# fpga-power.net
KiCad netlist of a schematic drawn in Altium Designer
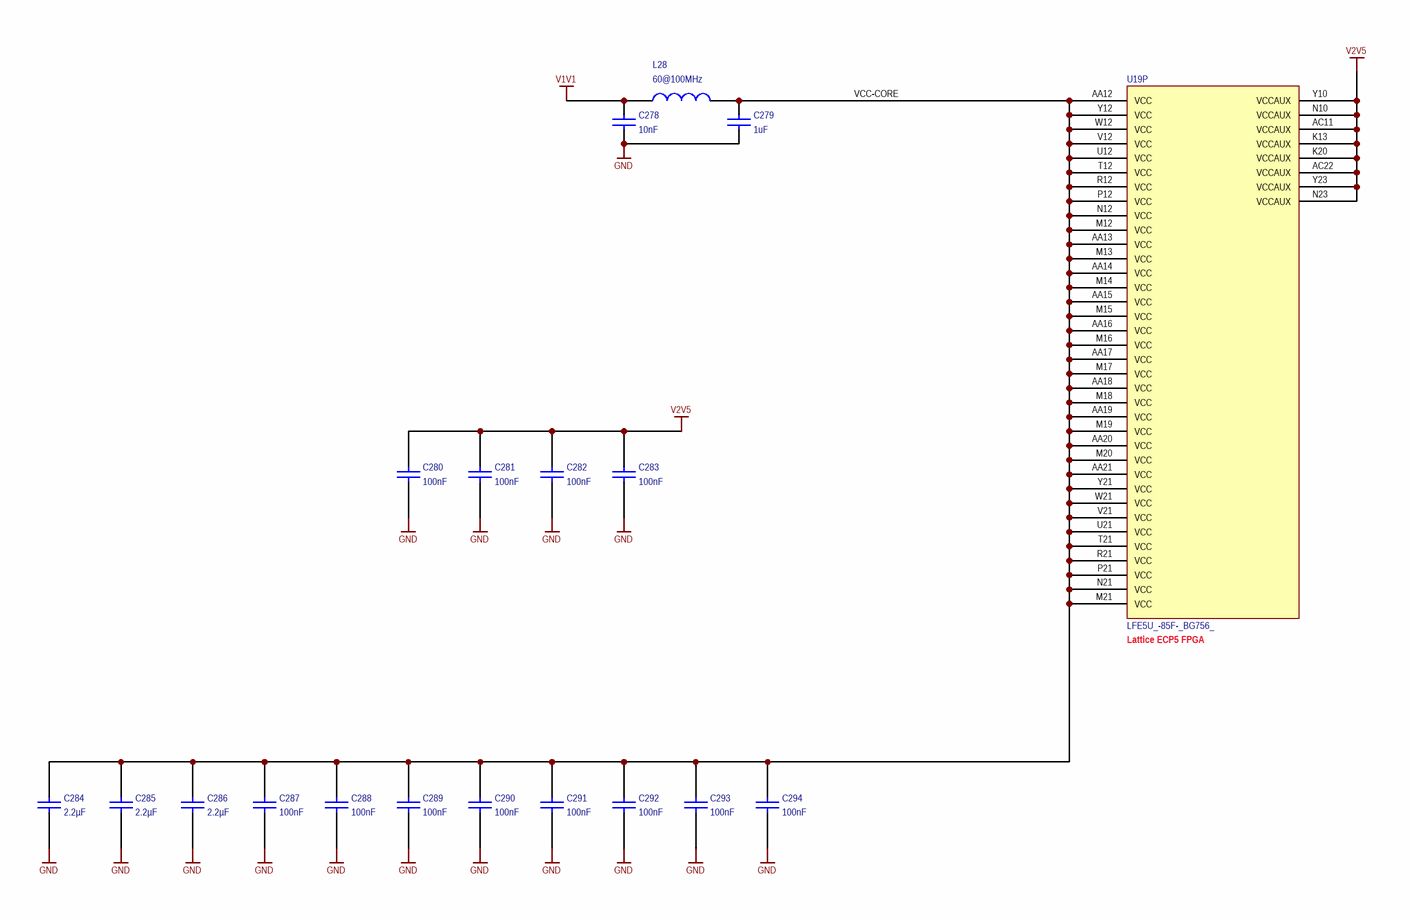
[diagram p0: fpga-power.SchDoc]

(export (version "E")
  (design (tool "Eeschema 10.0.6"))
  (components
    (comp (ref "C278")
      (value "10nF")
      (footprint "generic:0402")
      (description "Ceramic Capacitor 10nF ±10% 25V X7R 0402")
      (fields (field (name "VOLTAGE") "25V") (field (name "MANUFACTURER") "Murata"))
      (libsource (lib "Graviton") (part "CAP 0402"))
    )
    (comp (ref "C279")
      (value "1uF")
      (footprint "generic:0402")
      (description "Ceramic Capacitor 1uF ±10% 10V X5R 0402")
      (fields (field (name "VOLTAGE") "10V") (field (name "MANUFACTURER") "Murata"))
      (libsource (lib "Graviton") (part "CAP 0402"))
    )
    (comp (ref "C280")
      (value "100nF")
      (footprint "generic:CAPC1005X56N")
      (description "Ceramic Capacitor 100nF ±10% 16V X7R 0402")
      (fields (field (name "MANUFACTURER") "Murata") (field (name "TOLERANCE") "±10%"))
      (libsource (lib "murata") (part "GRM155R71A104KA01J"))
    )
    (comp (ref "C281")
      (value "100nF")
      (footprint "generic:CAPC1005X56N")
      (description "Ceramic Capacitor 100nF ±10% 16V X7R 0402")
      (fields (field (name "MANUFACTURER") "Murata") (field (name "TOLERANCE") "±10%"))
      (libsource (lib "murata") (part "GRM155R71A104KA01J"))
    )
    (comp (ref "C282")
      (value "100nF")
      (footprint "generic:CAPC1005X56N")
      (description "Ceramic Capacitor 100nF ±10% 16V X7R 0402")
      (fields (field (name "MANUFACTURER") "Murata") (field (name "TOLERANCE") "±10%"))
      (libsource (lib "murata") (part "GRM155R71A104KA01J"))
    )
    (comp (ref "C283")
      (value "100nF")
      (footprint "generic:CAPC1005X56N")
      (description "Ceramic Capacitor 100nF ±10% 16V X7R 0402")
      (fields (field (name "MANUFACTURER") "Murata") (field (name "TOLERANCE") "±10%"))
      (libsource (lib "murata") (part "GRM155R71A104KA01J"))
    )
    (comp (ref "C284")
      (value "2.2µF")
      (footprint "generic:CAPC1608X90N")
      (description "Ceramic Capacitor 2.2uF ±10% 10V X7R 0603")
      (fields (field (name "MANUFACTURER") "Murata") (field (name "TOLERANCE") "±10%"))
      (libsource (lib "murata") (part "GRM188R71A225KE15D"))
    )
    (comp (ref "C285")
      (value "2.2µF")
      (footprint "generic:CAPC1608X90N")
      (description "Ceramic Capacitor 2.2uF ±10% 10V X7R 0603")
      (fields (field (name "MANUFACTURER") "Murata") (field (name "TOLERANCE") "±10%"))
      (libsource (lib "murata") (part "GRM188R71A225KE15D"))
    )
    (comp (ref "C286")
      (value "2.2µF")
      (footprint "generic:CAPC1608X90N")
      (description "Ceramic Capacitor 2.2uF ±10% 10V X7R 0603")
      (fields (field (name "MANUFACTURER") "Murata") (field (name "TOLERANCE") "±10%"))
      (libsource (lib "murata") (part "GRM188R71A225KE15D"))
    )
    (comp (ref "C287")
      (value "100nF")
      (footprint "generic:CAPC1005X56N")
      (description "Ceramic Capacitor 100nF ±10% 16V X7R 0402")
      (fields (field (name "MANUFACTURER") "Murata") (field (name "TOLERANCE") "±10%"))
      (libsource (lib "murata") (part "GRM155R71A104KA01J"))
    )
    (comp (ref "C288")
      (value "100nF")
      (footprint "generic:CAPC1005X56N")
      (description "Ceramic Capacitor 100nF ±10% 16V X7R 0402")
      (fields (field (name "MANUFACTURER") "Murata") (field (name "TOLERANCE") "±10%"))
      (libsource (lib "murata") (part "GRM155R71A104KA01J"))
    )
    (comp (ref "C289")
      (value "100nF")
      (footprint "generic:CAPC1005X56N")
      (description "Ceramic Capacitor 100nF ±10% 16V X7R 0402")
      (fields (field (name "MANUFACTURER") "Murata") (field (name "TOLERANCE") "±10%"))
      (libsource (lib "murata") (part "GRM155R71A104KA01J"))
    )
    (comp (ref "C290")
      (value "100nF")
      (footprint "generic:CAPC1005X56N")
      (description "Ceramic Capacitor 100nF ±10% 16V X7R 0402")
      (fields (field (name "MANUFACTURER") "Murata") (field (name "TOLERANCE") "±10%"))
      (libsource (lib "murata") (part "GRM155R71A104KA01J"))
    )
    (comp (ref "C291")
      (value "100nF")
      (footprint "generic:CAPC1005X56N")
      (description "Ceramic Capacitor 100nF ±10% 16V X7R 0402")
      (fields (field (name "MANUFACTURER") "Murata") (field (name "TOLERANCE") "±10%"))
      (libsource (lib "murata") (part "GRM155R71A104KA01J"))
    )
    (comp (ref "C292")
      (value "100nF")
      (footprint "generic:CAPC1005X56N")
      (description "Ceramic Capacitor 100nF ±10% 16V X7R 0402")
      (fields (field (name "MANUFACTURER") "Murata") (field (name "TOLERANCE") "±10%"))
      (libsource (lib "murata") (part "GRM155R71A104KA01J"))
    )
    (comp (ref "C293")
      (value "100nF")
      (footprint "generic:CAPC1005X56N")
      (description "Ceramic Capacitor 100nF ±10% 16V X7R 0402")
      (fields (field (name "MANUFACTURER") "Murata") (field (name "TOLERANCE") "±10%"))
      (libsource (lib "murata") (part "GRM155R71A104KA01J"))
    )
    (comp (ref "C294")
      (value "100nF")
      (footprint "generic:CAPC1005X56N")
      (description "Ceramic Capacitor 100nF ±10% 16V X7R 0402")
      (fields (field (name "MANUFACTURER") "Murata") (field (name "TOLERANCE") "±10%"))
      (libsource (lib "murata") (part "GRM155R71A104KA01J"))
    )
    (comp (ref "L28")
      (value "60@100MHz")
      (footprint "0402")
      (description "Ferrite Bead 60-Ohm @ 100MHz 2.5A 0402")
      (fields (field (name "MANUFACTURER") "Murata") (field (name "TOLERANCE") "±25%"))
      (libsource (lib "Graviton") (part "IND 0402"))
    )
    (comp (ref "U19")
      (value "LFE5U_-85F-_BG756_")
      (footprint "lattice:caBGA756")
      (description "ECP5 FPGA, 85k LUT, 756-caBGA")
      (fields (field (name "MANUFACTURER") "Lattice Semiconductor"))
      (libsource (lib "lattice") (part "LFE5U_-85F-_BG756_"))
    )
  )
  (nets
    (net (code "1") (name "/VCC-CORE") (class "Default")
      (node (ref "C279") (pin "2") (pinfunction "2_2") (pintype "passive"))
      (node (ref "C284") (pin "2") (pinfunction "2_2") (pintype "passive"))
      (node (ref "C285") (pin "2") (pinfunction "2_2") (pintype "passive"))
      (node (ref "C286") (pin "2") (pinfunction "2_2") (pintype "passive"))
      (node (ref "C287") (pin "2") (pinfunction "2_2") (pintype "passive"))
      (node (ref "C288") (pin "2") (pinfunction "2_2") (pintype "passive"))
      (node (ref "C289") (pin "2") (pinfunction "2_2") (pintype "passive"))
      (node (ref "C290") (pin "2") (pinfunction "2_2") (pintype "passive"))
      (node (ref "C291") (pin "2") (pinfunction "2_2") (pintype "passive"))
      (node (ref "C292") (pin "2") (pinfunction "2_2") (pintype "passive"))
      (node (ref "C293") (pin "2") (pinfunction "2_2") (pintype "passive"))
      (node (ref "C294") (pin "2") (pinfunction "2_2") (pintype "passive"))
      (node (ref "L28") (pin "2") (pinfunction "2_2") (pintype "passive"))
      (node (ref "U19") (pin "AA12") (pinfunction "VCC_AA12") (pintype "power_in"))
      (node (ref "U19") (pin "AA13") (pinfunction "VCC_AA13") (pintype "power_in"))
      (node (ref "U19") (pin "AA14") (pinfunction "VCC_AA14") (pintype "power_in"))
      (node (ref "U19") (pin "AA15") (pinfunction "VCC_AA15") (pintype "power_in"))
      (node (ref "U19") (pin "AA16") (pinfunction "VCC_AA16") (pintype "power_in"))
      (node (ref "U19") (pin "AA17") (pinfunction "VCC_AA17") (pintype "power_in"))
      (node (ref "U19") (pin "AA18") (pinfunction "VCC_AA18") (pintype "power_in"))
      (node (ref "U19") (pin "AA19") (pinfunction "VCC_AA19") (pintype "power_in"))
      (node (ref "U19") (pin "AA20") (pinfunction "VCC_AA20") (pintype "power_in"))
      (node (ref "U19") (pin "AA21") (pinfunction "VCC_AA21") (pintype "power_in"))
      (node (ref "U19") (pin "M12") (pinfunction "VCC_M12") (pintype "power_in"))
      (node (ref "U19") (pin "M13") (pinfunction "VCC_M13") (pintype "power_in"))
      (node (ref "U19") (pin "M14") (pinfunction "VCC_M14") (pintype "power_in"))
      (node (ref "U19") (pin "M15") (pinfunction "VCC_M15") (pintype "power_in"))
      (node (ref "U19") (pin "M16") (pinfunction "VCC_M16") (pintype "power_in"))
      (node (ref "U19") (pin "M17") (pinfunction "VCC_M17") (pintype "power_in"))
      (node (ref "U19") (pin "M18") (pinfunction "VCC_M18") (pintype "power_in"))
      (node (ref "U19") (pin "M19") (pinfunction "VCC_M19") (pintype "power_in"))
      (node (ref "U19") (pin "M20") (pinfunction "VCC_M20") (pintype "power_in"))
      (node (ref "U19") (pin "M21") (pinfunction "VCC_M21") (pintype "power_in"))
      (node (ref "U19") (pin "N12") (pinfunction "VCC_N12") (pintype "power_in"))
      (node (ref "U19") (pin "N21") (pinfunction "VCC_N21") (pintype "power_in"))
      (node (ref "U19") (pin "P12") (pinfunction "VCC_P12") (pintype "power_in"))
      (node (ref "U19") (pin "P21") (pinfunction "VCC_P21") (pintype "power_in"))
      (node (ref "U19") (pin "R12") (pinfunction "VCC_R12") (pintype "power_in"))
      (node (ref "U19") (pin "R21") (pinfunction "VCC_R21") (pintype "power_in"))
      (node (ref "U19") (pin "T12") (pinfunction "VCC_T12") (pintype "power_in"))
      (node (ref "U19") (pin "T21") (pinfunction "VCC_T21") (pintype "power_in"))
      (node (ref "U19") (pin "U12") (pinfunction "VCC_U12") (pintype "power_in"))
      (node (ref "U19") (pin "U21") (pinfunction "VCC_U21") (pintype "power_in"))
      (node (ref "U19") (pin "V12") (pinfunction "VCC_V12") (pintype "power_in"))
      (node (ref "U19") (pin "V21") (pinfunction "VCC_V21") (pintype "power_in"))
      (node (ref "U19") (pin "W12") (pinfunction "VCC_W12") (pintype "power_in"))
      (node (ref "U19") (pin "W21") (pinfunction "VCC_W21") (pintype "power_in"))
      (node (ref "U19") (pin "Y12") (pinfunction "VCC_Y12") (pintype "power_in"))
      (node (ref "U19") (pin "Y21") (pinfunction "VCC_Y21") (pintype "power_in"))
    )
    (net (code "2") (name "GND") (class "Default")
      (node (ref "C278") (pin "1") (pinfunction "1_1") (pintype "passive"))
      (node (ref "C279") (pin "1") (pinfunction "1_1") (pintype "passive"))
      (node (ref "C280") (pin "1") (pinfunction "1_1") (pintype "passive"))
      (node (ref "C281") (pin "1") (pinfunction "1_1") (pintype "passive"))
      (node (ref "C282") (pin "1") (pinfunction "1_1") (pintype "passive"))
      (node (ref "C283") (pin "1") (pinfunction "1_1") (pintype "passive"))
      (node (ref "C284") (pin "1") (pinfunction "1_1") (pintype "passive"))
      (node (ref "C285") (pin "1") (pinfunction "1_1") (pintype "passive"))
      (node (ref "C286") (pin "1") (pinfunction "1_1") (pintype "passive"))
      (node (ref "C287") (pin "1") (pinfunction "1_1") (pintype "passive"))
      (node (ref "C288") (pin "1") (pinfunction "1_1") (pintype "passive"))
      (node (ref "C289") (pin "1") (pinfunction "1_1") (pintype "passive"))
      (node (ref "C290") (pin "1") (pinfunction "1_1") (pintype "passive"))
      (node (ref "C291") (pin "1") (pinfunction "1_1") (pintype "passive"))
      (node (ref "C292") (pin "1") (pinfunction "1_1") (pintype "passive"))
      (node (ref "C293") (pin "1") (pinfunction "1_1") (pintype "passive"))
      (node (ref "C294") (pin "1") (pinfunction "1_1") (pintype "passive"))
    )
    (net (code "3") (name "V1V1") (class "Default")
      (node (ref "C278") (pin "2") (pinfunction "2_2") (pintype "passive"))
      (node (ref "L28") (pin "1") (pinfunction "1_1") (pintype "passive"))
    )
    (net (code "4") (name "V2V5") (class "Default")
      (node (ref "C280") (pin "2") (pinfunction "2_2") (pintype "passive"))
      (node (ref "C281") (pin "2") (pinfunction "2_2") (pintype "passive"))
      (node (ref "C282") (pin "2") (pinfunction "2_2") (pintype "passive"))
      (node (ref "C283") (pin "2") (pinfunction "2_2") (pintype "passive"))
      (node (ref "U19") (pin "AC11") (pinfunction "VCCAUX_AC11") (pintype "power_in"))
      (node (ref "U19") (pin "AC22") (pinfunction "VCCAUX_AC22") (pintype "power_in"))
      (node (ref "U19") (pin "K13") (pinfunction "VCCAUX_K13") (pintype "power_in"))
      (node (ref "U19") (pin "K20") (pinfunction "VCCAUX_K20") (pintype "power_in"))
      (node (ref "U19") (pin "N10") (pinfunction "VCCAUX_N10") (pintype "power_in"))
      (node (ref "U19") (pin "N23") (pinfunction "VCCAUX_N23") (pintype "power_in"))
      (node (ref "U19") (pin "Y10") (pinfunction "VCCAUX_Y10") (pintype "power_in"))
      (node (ref "U19") (pin "Y23") (pinfunction "VCCAUX_Y23") (pintype "power_in"))
    )
  )
)
